# PDC_high_Current_Outputs.net
KiCad netlist of a schematic drawn in Altium Designer
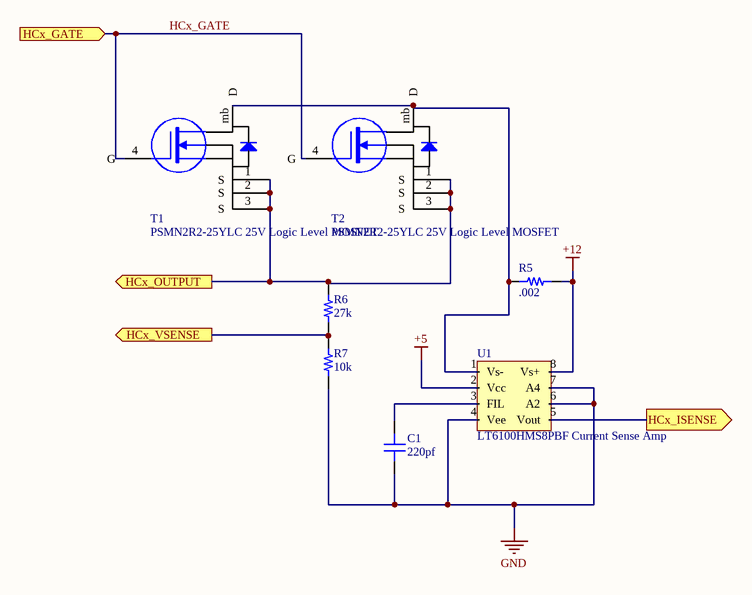
[diagram p0: PDC_high_Current_Outputs.SchDoc]

(export (version "E")
  (design (tool "Eeschema 10.0.6"))
  (components
    (comp (ref "C1")
      (value "220pf")
      (footprint "CAP 0402/1005")
      (fields
        (field (name "Comment") "Capacitor MLCC 220pf 16V CAP 0402/1005")
        (field (name "CREATED_BY") "Nick Mah")
      )
      (libsource (lib "Altium-Lib") (part "Capacitor"))
    )
    (comp (ref "R5")
      (value ".002")
      (footprint "RES 2010/5025")
      (description "Current Sense Resistor")
      (fields
        (field (name "TOLERANCE") "1%")
        (field (name "POWER") "1.5W")
        (field (name "CREATED_BY") "Angel")
      )
      (libsource (lib "Altium-Lib") (part "Resistor"))
    )
    (comp (ref "R6")
      (value "27k")
      (footprint "RES 0805/2012")
      (fields
        (field (name "TOLERANCE") "10%")
        (field (name "POWER") "1/10W")
        (field (name "Comment") "Resistor 27k 0805 1/10W 10%")
        (field (name "CREATED_BY") "Nick Mah")
      )
      (libsource (lib "") (part "Resistor_1"))
    )
    (comp (ref "R7")
      (value "10k")
      (footprint "RES 0402/1005")
      (fields
        (field (name "TOLERANCE") "1%")
        (field (name "POWER") "1/10W")
        (field (name "Comment") "Resistor 10k 0402 1/10W 1%")
        (field (name "CREATED_BY") "Nick Mah")
      )
      (libsource (lib "") (part "Resistor_1"))
    )
    (comp (ref "T1")
      (value "PSMN2R2-25YLC 25V Logic Level MOSFET")
      (footprint "LFPAK-SO8")
      (description "N-Channel 25V 100A (Tc) 106W (Tc) Surface Mount LFPAK56, Power-SO8")
      (fields (field (name "MFRPARTNO") "PSMN2R2-25YLC,115") (field (name "CREATED_BY") "Nick"))
      (libsource (lib "Altium-Lib") (part "PSMN2R2-25YLC 25V Logic Level MOSFET"))
    )
    (comp (ref "T2")
      (value "PSMN2R2-25YLC 25V Logic Level MOSFET")
      (footprint "LFPAK-SO8")
      (description "N-Channel 25V 100A (Tc) 106W (Tc) Surface Mount LFPAK56, Power-SO8")
      (fields (field (name "MFRPARTNO") "PSMN2R2-25YLC,115") (field (name "CREATED_BY") "Nick"))
      (libsource (lib "Altium-Lib") (part "PSMN2R2-25YLC 25V Logic Level MOSFET"))
    )
    (comp (ref "U1")
      (value "LT6100HMS8PBF Current Sense Amp")
      (footprint "MSOP-8")
      (fields (field (name "CREATED_BY") "Eddy"))
      (libsource (lib "Altium-Lib") (part "LT6100HMS8PBF Current Sense Amp"))
    )
  )
  (nets
    (net (code "1") (name "+5") (class "Default")
      (node (ref "U1") (pin "2") (pinfunction "Vcc_2") (pintype "input"))
    )
    (net (code "2") (name "+12") (class "Default")
      (node (ref "R5") (pin "2") (pinfunction "2_2") (pintype "passive"))
      (node (ref "U1") (pin "8") (pinfunction "Vs+_8") (pintype "input"))
    )
    (net (code "3") (name "/HCx_GATE") (class "Default")
      (node (ref "T1") (pin "4") (pinfunction "G_4") (pintype "passive"))
      (node (ref "T2") (pin "4") (pinfunction "G_4") (pintype "passive"))
    )
    (net (code "4") (name "/HCx_ISENSE") (class "Default")
      (node (ref "U1") (pin "5") (pinfunction "Vout_5") (pintype "input"))
    )
    (net (code "5") (name "/HCx_OUTPUT") (class "Default")
      (node (ref "R6") (pin "2") (pinfunction "2_2") (pintype "passive"))
      (node (ref "T1") (pin "1") (pinfunction "S_1") (pintype "passive"))
      (node (ref "T1") (pin "2") (pinfunction "S_2") (pintype "passive"))
      (node (ref "T1") (pin "3") (pinfunction "S_3") (pintype "passive"))
      (node (ref "T2") (pin "1") (pinfunction "S_1") (pintype "passive"))
      (node (ref "T2") (pin "2") (pinfunction "S_2") (pintype "passive"))
      (node (ref "T2") (pin "3") (pinfunction "S_3") (pintype "passive"))
    )
    (net (code "6") (name "/HCx_VSENSE") (class "Default")
      (node (ref "R6") (pin "1") (pinfunction "1_1") (pintype "passive"))
      (node (ref "R7") (pin "2") (pinfunction "2_2") (pintype "passive"))
    )
    (net (code "7") (name "GND") (class "Default")
      (node (ref "C1") (pin "1") (pinfunction "1_1") (pintype "passive"))
      (node (ref "R7") (pin "1") (pinfunction "1_1") (pintype "passive"))
      (node (ref "U1") (pin "4") (pinfunction "Vee_4") (pintype "input"))
      (node (ref "U1") (pin "6") (pinfunction "A2_6") (pintype "input"))
      (node (ref "U1") (pin "7") (pinfunction "A4_7") (pintype "input"))
    )
    (net (code "8") (name "Net-(T1-D)") (class "Default")
      (node (ref "R5") (pin "1") (pinfunction "1_1") (pintype "passive"))
      (node (ref "T1") (pin "mb") (pinfunction "D_mb") (pintype "passive"))
      (node (ref "T2") (pin "mb") (pinfunction "D_mb") (pintype "passive"))
      (node (ref "U1") (pin "1") (pinfunction "Vs-_1") (pintype "input"))
    )
    (net (code "9") (name "Net-(U1-FIL)") (class "Default")
      (node (ref "C1") (pin "2") (pinfunction "2_2") (pintype "passive"))
      (node (ref "U1") (pin "3") (pinfunction "FIL_3") (pintype "input"))
    )
  )
)
